# Tester.net
KiCad netlist of a schematic drawn in EAGLE
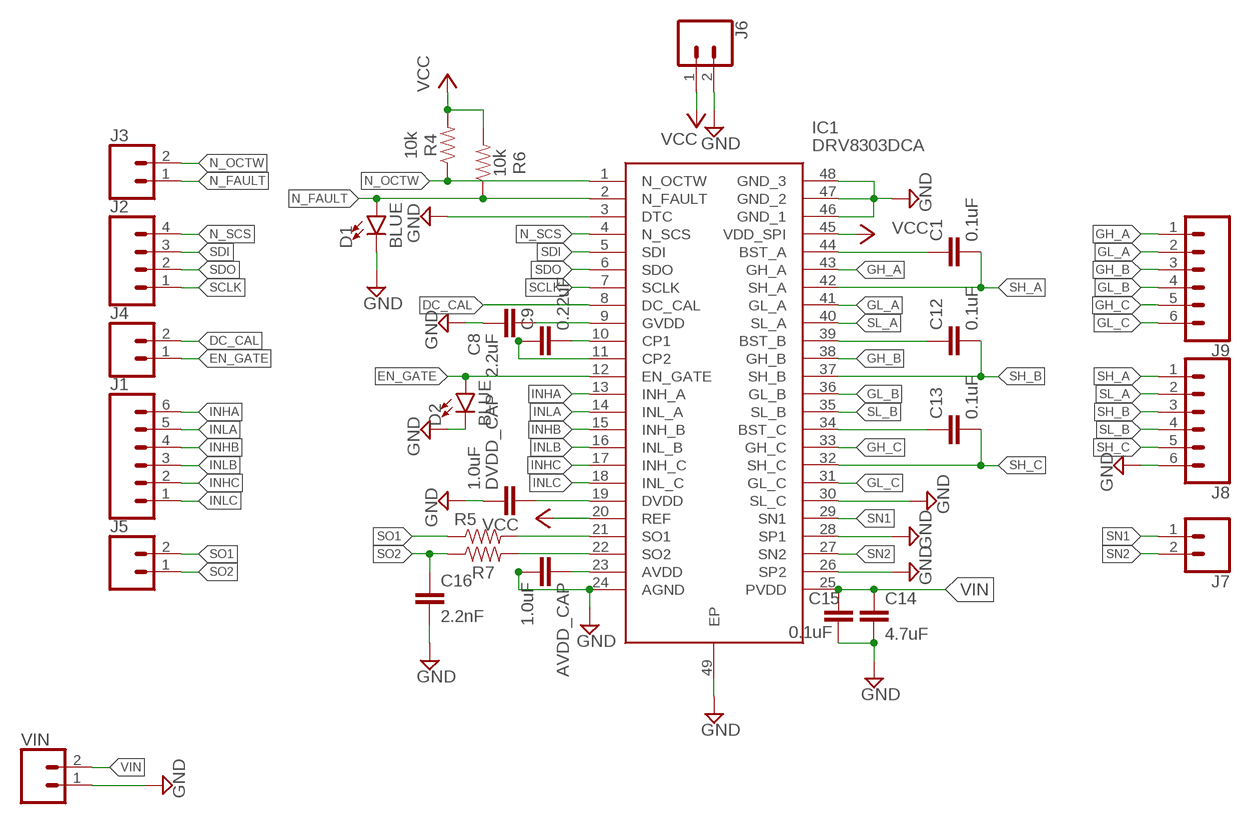
[diagram p0: schematic, sheet 1]

(export (version "E")
  (design (tool "Eeschema 10.0.6"))
  (components
    (comp (ref "AVDD_CAP")
      (value "1.0uF")
      (footprint "eagle-import:0603")
      (libsource (lib "eagle-import") (part "1.0UF-0603-16V-10%"))
    )
    (comp (ref "C1")
      (value "0.1uF")
      (footprint "eagle-import:0603")
      (libsource (lib "eagle-import") (part "0.1UF-0603-25V-(+80/-20%)"))
    )
    (comp (ref "C8")
      (value "2.2uF")
      (footprint "eagle-import:0603")
      (libsource (lib "eagle-import") (part "2.2UF-0603-10V-20%"))
    )
    (comp (ref "C9")
      (value "0.22uF")
      (footprint "eagle-import:0603")
      (libsource (lib "eagle-import") (part "0.22UF-0603-25V-10%"))
    )
    (comp (ref "C12")
      (value "0.1uF")
      (footprint "eagle-import:0603")
      (libsource (lib "eagle-import") (part "0.1UF-0603-25V-(+80/-20%)"))
    )
    (comp (ref "C13")
      (value "0.1uF")
      (footprint "eagle-import:0603")
      (libsource (lib "eagle-import") (part "0.1UF-0603-25V-(+80/-20%)"))
    )
    (comp (ref "C14")
      (value "4.7uF")
      (footprint "eagle-import:0603")
      (libsource (lib "eagle-import") (part "4.7UF-0603-35V-(20%)"))
    )
    (comp (ref "C15")
      (value "0.1uF")
      (footprint "eagle-import:0603")
      (libsource (lib "eagle-import") (part "0.1UF-0603-25V-(+80/-20%)"))
    )
    (comp (ref "C16")
      (value "2.2nF")
      (footprint "eagle-import:0603")
      (libsource (lib "eagle-import") (part "2.2NF/2200PF-0603-50V-10%"))
    )
    (comp (ref "D1")
      (value "BLUE")
      (footprint "eagle-import:LED-0603")
      (libsource (lib "eagle-import") (part "LED-BLUE0603"))
    )
    (comp (ref "D2")
      (value "BLUE")
      (footprint "eagle-import:LED-0603")
      (libsource (lib "eagle-import") (part "LED-BLUE0603"))
    )
    (comp (ref "DVDD_CAP")
      (value "1.0uF")
      (footprint "eagle-import:0603")
      (libsource (lib "eagle-import") (part "1.0UF-0603-16V-10%"))
    )
    (comp (ref "IC1")
      (value "DRV8303DCA")
      (footprint "eagle-import:SOP50P810X120-49N")
      (fields (field (name "MOUSER_PART_NUMBER") "595-DRV8303DCA"))
      (libsource (lib "eagle-import") (part "DRV8303DCA"))
    )
    (comp (ref "J1")
      (value "CONN_06SILK_FEMALE_PTH")
      (footprint "eagle-import:1X06")
      (libsource (lib "eagle-import") (part "CONN_06SILK_FEMALE_PTH"))
    )
    (comp (ref "J2")
      (value "CONN_04PTH")
      (footprint "eagle-import:1X04")
      (libsource (lib "eagle-import") (part "CONN_04PTH"))
    )
    (comp (ref "J3")
      (value "CONN_02")
      (footprint "eagle-import:1X02")
      (libsource (lib "eagle-import") (part "CONN_02"))
    )
    (comp (ref "J4")
      (value "CONN_02")
      (footprint "eagle-import:1X02")
      (libsource (lib "eagle-import") (part "CONN_02"))
    )
    (comp (ref "J5")
      (value "CONN_02")
      (footprint "eagle-import:1X02")
      (libsource (lib "eagle-import") (part "CONN_02"))
    )
    (comp (ref "J6")
      (value "CONN_02")
      (footprint "eagle-import:1X02")
      (libsource (lib "eagle-import") (part "CONN_02"))
    )
    (comp (ref "J7")
      (value "CONN_02")
      (footprint "eagle-import:1X02")
      (libsource (lib "eagle-import") (part "CONN_02"))
    )
    (comp (ref "J8")
      (value "CONN_06SILK_FEMALE_PTH")
      (footprint "eagle-import:1X06")
      (libsource (lib "eagle-import") (part "CONN_06SILK_FEMALE_PTH"))
    )
    (comp (ref "J9")
      (value "CONN_06SILK_FEMALE_PTH")
      (footprint "eagle-import:1X06")
      (libsource (lib "eagle-import") (part "CONN_06SILK_FEMALE_PTH"))
    )
    (comp (ref "R4")
      (value "10k")
      (footprint "eagle-import:0603")
      (libsource (lib "eagle-import") (part "10KOHM-0603-1/10W-1%"))
    )
    (comp (ref "R5")
      (value "0")
      (footprint "eagle-import:0603")
      (libsource (lib "eagle-import") (part "0OHM-0603-1/10W"))
    )
    (comp (ref "R6")
      (value "10k")
      (footprint "eagle-import:0603")
      (libsource (lib "eagle-import") (part "10KOHM-0603-1/10W-1%"))
    )
    (comp (ref "R7")
      (value "0")
      (footprint "eagle-import:0603")
      (libsource (lib "eagle-import") (part "0OHM-0603-1/10W"))
    )
    (comp (ref "VIN")
      (value "CONN_02LOCK_LONGPADS")
      (footprint "eagle-import:1X02_LOCK_LONGPADS")
      (libsource (lib "eagle-import") (part "CONN_02LOCK_LONGPADS"))
    )
  )
  (nets
    (net (code "1") (name "DC_CAL") (class "Default")
      (node (ref "IC1") (pin "8") (pinfunction "DC_CAL_8") (pintype "input"))
      (node (ref "J4") (pin "2") (pinfunction "2_2") (pintype "passive"))
    )
    (net (code "2") (name "EN_GATE") (class "Default")
      (node (ref "D2") (pin "A") (pinfunction "A_A") (pintype "passive"))
      (node (ref "IC1") (pin "12") (pinfunction "EN_GATE_12") (pintype "input"))
      (node (ref "J4") (pin "1") (pinfunction "1_1") (pintype "passive"))
    )
    (net (code "3") (name "GH_A") (class "Default")
      (node (ref "IC1") (pin "43") (pinfunction "GH_A_43") (pintype "output"))
      (node (ref "J9") (pin "1") (pinfunction "1_1") (pintype "passive"))
    )
    (net (code "4") (name "GH_B") (class "Default")
      (node (ref "IC1") (pin "38") (pinfunction "GH_B_38") (pintype "output"))
      (node (ref "J9") (pin "3") (pinfunction "3_3") (pintype "passive"))
    )
    (net (code "5") (name "GH_C") (class "Default")
      (node (ref "IC1") (pin "33") (pinfunction "GH_C_33") (pintype "output"))
      (node (ref "J9") (pin "5") (pinfunction "5_5") (pintype "passive"))
    )
    (net (code "6") (name "GL_A") (class "Default")
      (node (ref "IC1") (pin "41") (pinfunction "GL_A_41") (pintype "output"))
      (node (ref "J9") (pin "2") (pinfunction "2_2") (pintype "passive"))
    )
    (net (code "7") (name "GL_B") (class "Default")
      (node (ref "IC1") (pin "36") (pinfunction "GL_B_36") (pintype "output"))
      (node (ref "J9") (pin "4") (pinfunction "4_4") (pintype "passive"))
    )
    (net (code "8") (name "GL_C") (class "Default")
      (node (ref "IC1") (pin "31") (pinfunction "GL_C_31") (pintype "output"))
      (node (ref "J9") (pin "6") (pinfunction "6_6") (pintype "passive"))
    )
    (net (code "9") (name "GND") (class "Default")
      (node (ref "AVDD_CAP") (pin "2") (pinfunction "2_2") (pintype "passive"))
      (node (ref "C14") (pin "2") (pinfunction "2_2") (pintype "passive"))
      (node (ref "C15") (pin "2") (pinfunction "2_2") (pintype "passive"))
      (node (ref "C16") (pin "2") (pinfunction "2_2") (pintype "passive"))
      (node (ref "C8") (pin "2") (pinfunction "2_2") (pintype "passive"))
      (node (ref "D1") (pin "C") (pinfunction "C_C") (pintype "passive"))
      (node (ref "D2") (pin "C") (pinfunction "C_C") (pintype "passive"))
      (node (ref "DVDD_CAP") (pin "1") (pinfunction "1_1") (pintype "passive"))
      (node (ref "IC1") (pin "24") (pinfunction "AGND_24") (pintype "power_in"))
      (node (ref "IC1") (pin "26") (pinfunction "SP2_26") (pintype "input"))
      (node (ref "IC1") (pin "28") (pinfunction "SP1_28") (pintype "input"))
      (node (ref "IC1") (pin "3") (pinfunction "DTC_3") (pintype "input"))
      (node (ref "IC1") (pin "30") (pinfunction "SL_C_30") (pintype "input"))
      (node (ref "IC1") (pin "46") (pinfunction "GND_1_46") (pintype "power_in"))
      (node (ref "IC1") (pin "47") (pinfunction "GND_2_47") (pintype "power_in"))
      (node (ref "IC1") (pin "48") (pinfunction "GND_3_48") (pintype "power_in"))
      (node (ref "IC1") (pin "49") (pinfunction "EP_49") (pintype "bidirectional"))
      (node (ref "J6") (pin "2") (pinfunction "2_2") (pintype "passive"))
      (node (ref "J8") (pin "6") (pinfunction "6_6") (pintype "passive"))
      (node (ref "VIN") (pin "1") (pinfunction "1_1") (pintype "passive"))
    )
    (net (code "10") (name "INHA") (class "Default")
      (node (ref "IC1") (pin "13") (pinfunction "INH_A_13") (pintype "input"))
      (node (ref "J1") (pin "6") (pinfunction "6_6") (pintype "passive"))
    )
    (net (code "11") (name "INHB") (class "Default")
      (node (ref "IC1") (pin "15") (pinfunction "INH_B_15") (pintype "input"))
      (node (ref "J1") (pin "4") (pinfunction "4_4") (pintype "passive"))
    )
    (net (code "12") (name "INHC") (class "Default")
      (node (ref "IC1") (pin "17") (pinfunction "INH_C_17") (pintype "input"))
      (node (ref "J1") (pin "2") (pinfunction "2_2") (pintype "passive"))
    )
    (net (code "13") (name "INLA") (class "Default")
      (node (ref "IC1") (pin "14") (pinfunction "INL_A_14") (pintype "input"))
      (node (ref "J1") (pin "5") (pinfunction "5_5") (pintype "passive"))
    )
    (net (code "14") (name "INLB") (class "Default")
      (node (ref "IC1") (pin "16") (pinfunction "INL_B_16") (pintype "input"))
      (node (ref "J1") (pin "3") (pinfunction "3_3") (pintype "passive"))
    )
    (net (code "15") (name "INLC") (class "Default")
      (node (ref "IC1") (pin "18") (pinfunction "INL_C_18") (pintype "input"))
      (node (ref "J1") (pin "1") (pinfunction "1_1") (pintype "passive"))
    )
    (net (code "16") (name "N_FAULT") (class "Default")
      (node (ref "D1") (pin "A") (pinfunction "A_A") (pintype "passive"))
      (node (ref "IC1") (pin "2") (pinfunction "N_FAULT_2") (pintype "output"))
      (node (ref "J3") (pin "1") (pinfunction "1_1") (pintype "passive"))
      (node (ref "R6") (pin "1") (pinfunction "1_1") (pintype "passive"))
    )
    (net (code "17") (name "N_OCTW") (class "Default")
      (node (ref "IC1") (pin "1") (pinfunction "N_OCTW_1") (pintype "output"))
      (node (ref "J3") (pin "2") (pinfunction "2_2") (pintype "passive"))
      (node (ref "R4") (pin "1") (pinfunction "1_1") (pintype "passive"))
    )
    (net (code "18") (name "N_SCS") (class "Default")
      (node (ref "IC1") (pin "4") (pinfunction "N_SCS_4") (pintype "input"))
      (node (ref "J2") (pin "4") (pinfunction "4_4") (pintype "passive"))
    )
    (net (code "19") (name "Net-(IC1-AVDD)") (class "Default")
      (node (ref "AVDD_CAP") (pin "1") (pinfunction "1_1") (pintype "passive"))
      (node (ref "IC1") (pin "23") (pinfunction "AVDD_23") (pintype "power_in"))
    )
    (net (code "20") (name "Net-(IC1-BST_A)") (class "Default")
      (node (ref "C1") (pin "1") (pinfunction "1_1") (pintype "passive"))
      (node (ref "IC1") (pin "44") (pinfunction "BST_A_44") (pintype "bidirectional"))
    )
    (net (code "21") (name "Net-(IC1-BST_B)") (class "Default")
      (node (ref "C12") (pin "1") (pinfunction "1_1") (pintype "passive"))
      (node (ref "IC1") (pin "39") (pinfunction "BST_B_39") (pintype "bidirectional"))
    )
    (net (code "22") (name "Net-(IC1-BST_C)") (class "Default")
      (node (ref "C13") (pin "1") (pinfunction "1_1") (pintype "passive"))
      (node (ref "IC1") (pin "34") (pinfunction "BST_C_34") (pintype "bidirectional"))
    )
    (net (code "23") (name "Net-(IC1-CP1)") (class "Default")
      (node (ref "C9") (pin "2") (pinfunction "2_2") (pintype "passive"))
      (node (ref "IC1") (pin "10") (pinfunction "CP1_10") (pintype "power_in"))
    )
    (net (code "24") (name "Net-(IC1-CP2)") (class "Default")
      (node (ref "C9") (pin "1") (pinfunction "1_1") (pintype "passive"))
      (node (ref "IC1") (pin "11") (pinfunction "CP2_11") (pintype "power_in"))
    )
    (net (code "25") (name "Net-(IC1-DVDD)") (class "Default")
      (node (ref "DVDD_CAP") (pin "2") (pinfunction "2_2") (pintype "passive"))
      (node (ref "IC1") (pin "19") (pinfunction "DVDD_19") (pintype "power_in"))
    )
    (net (code "26") (name "Net-(IC1-GVDD)") (class "Default")
      (node (ref "C8") (pin "1") (pinfunction "1_1") (pintype "passive"))
      (node (ref "IC1") (pin "9") (pinfunction "GVDD_9") (pintype "power_in"))
    )
    (net (code "27") (name "Net-(IC1-SO1)") (class "Default")
      (node (ref "IC1") (pin "21") (pinfunction "SO1_21") (pintype "output"))
      (node (ref "R5") (pin "2") (pinfunction "2_2") (pintype "passive"))
    )
    (net (code "28") (name "Net-(IC1-SO2)") (class "Default")
      (node (ref "IC1") (pin "22") (pinfunction "SO2_22") (pintype "output"))
      (node (ref "R7") (pin "2") (pinfunction "2_2") (pintype "passive"))
    )
    (net (code "29") (name "SCLK") (class "Default")
      (node (ref "IC1") (pin "7") (pinfunction "SCLK_7") (pintype "input"))
      (node (ref "J2") (pin "1") (pinfunction "1_1") (pintype "passive"))
    )
    (net (code "30") (name "SDI") (class "Default")
      (node (ref "IC1") (pin "5") (pinfunction "SDI_5") (pintype "input"))
      (node (ref "J2") (pin "3") (pinfunction "3_3") (pintype "passive"))
    )
    (net (code "31") (name "SDO") (class "Default")
      (node (ref "IC1") (pin "6") (pinfunction "SDO_6") (pintype "output"))
      (node (ref "J2") (pin "2") (pinfunction "2_2") (pintype "passive"))
    )
    (net (code "32") (name "SH_A") (class "Default")
      (node (ref "C1") (pin "2") (pinfunction "2_2") (pintype "passive"))
      (node (ref "IC1") (pin "42") (pinfunction "SH_A_42") (pintype "input"))
      (node (ref "J8") (pin "1") (pinfunction "1_1") (pintype "passive"))
    )
    (net (code "33") (name "SH_B") (class "Default")
      (node (ref "C12") (pin "2") (pinfunction "2_2") (pintype "passive"))
      (node (ref "IC1") (pin "37") (pinfunction "SH_B_37") (pintype "input"))
      (node (ref "J8") (pin "3") (pinfunction "3_3") (pintype "passive"))
    )
    (net (code "34") (name "SH_C") (class "Default")
      (node (ref "C13") (pin "2") (pinfunction "2_2") (pintype "passive"))
      (node (ref "IC1") (pin "32") (pinfunction "SH_C_32") (pintype "input"))
      (node (ref "J8") (pin "5") (pinfunction "5_5") (pintype "passive"))
    )
    (net (code "35") (name "SL_A") (class "Default")
      (node (ref "IC1") (pin "40") (pinfunction "SL_A_40") (pintype "input"))
      (node (ref "J8") (pin "2") (pinfunction "2_2") (pintype "passive"))
    )
    (net (code "36") (name "SL_B") (class "Default")
      (node (ref "IC1") (pin "35") (pinfunction "SL_B_35") (pintype "input"))
      (node (ref "J8") (pin "4") (pinfunction "4_4") (pintype "passive"))
    )
    (net (code "37") (name "SN1") (class "Default")
      (node (ref "IC1") (pin "29") (pinfunction "SN1_29") (pintype "input"))
      (node (ref "J7") (pin "1") (pinfunction "1_1") (pintype "passive"))
    )
    (net (code "38") (name "SN2") (class "Default")
      (node (ref "IC1") (pin "27") (pinfunction "SN2_27") (pintype "input"))
      (node (ref "J7") (pin "2") (pinfunction "2_2") (pintype "passive"))
    )
    (net (code "39") (name "SO1") (class "Default")
      (node (ref "J5") (pin "2") (pinfunction "2_2") (pintype "passive"))
      (node (ref "R5") (pin "1") (pinfunction "1_1") (pintype "passive"))
    )
    (net (code "40") (name "SO2") (class "Default")
      (node (ref "C16") (pin "1") (pinfunction "1_1") (pintype "passive"))
      (node (ref "J5") (pin "1") (pinfunction "1_1") (pintype "passive"))
      (node (ref "R7") (pin "1") (pinfunction "1_1") (pintype "passive"))
    )
    (net (code "41") (name "VCC") (class "Default")
      (node (ref "IC1") (pin "20") (pinfunction "REF_20") (pintype "input"))
      (node (ref "IC1") (pin "45") (pinfunction "VDD_SPI_45") (pintype "power_in"))
      (node (ref "J6") (pin "1") (pinfunction "1_1") (pintype "passive"))
      (node (ref "R4") (pin "2") (pinfunction "2_2") (pintype "passive"))
      (node (ref "R6") (pin "2") (pinfunction "2_2") (pintype "passive"))
    )
    (net (code "42") (name "VIN") (class "Default")
      (node (ref "C14") (pin "1") (pinfunction "1_1") (pintype "passive"))
      (node (ref "C15") (pin "1") (pinfunction "1_1") (pintype "passive"))
      (node (ref "IC1") (pin "25") (pinfunction "PVDD_25") (pintype "power_in"))
      (node (ref "VIN") (pin "2") (pinfunction "2_2") (pintype "passive"))
    )
  )
)
